# MCU_adacus_sch.net
KiCad netlist of a schematic drawn in Altium Designer
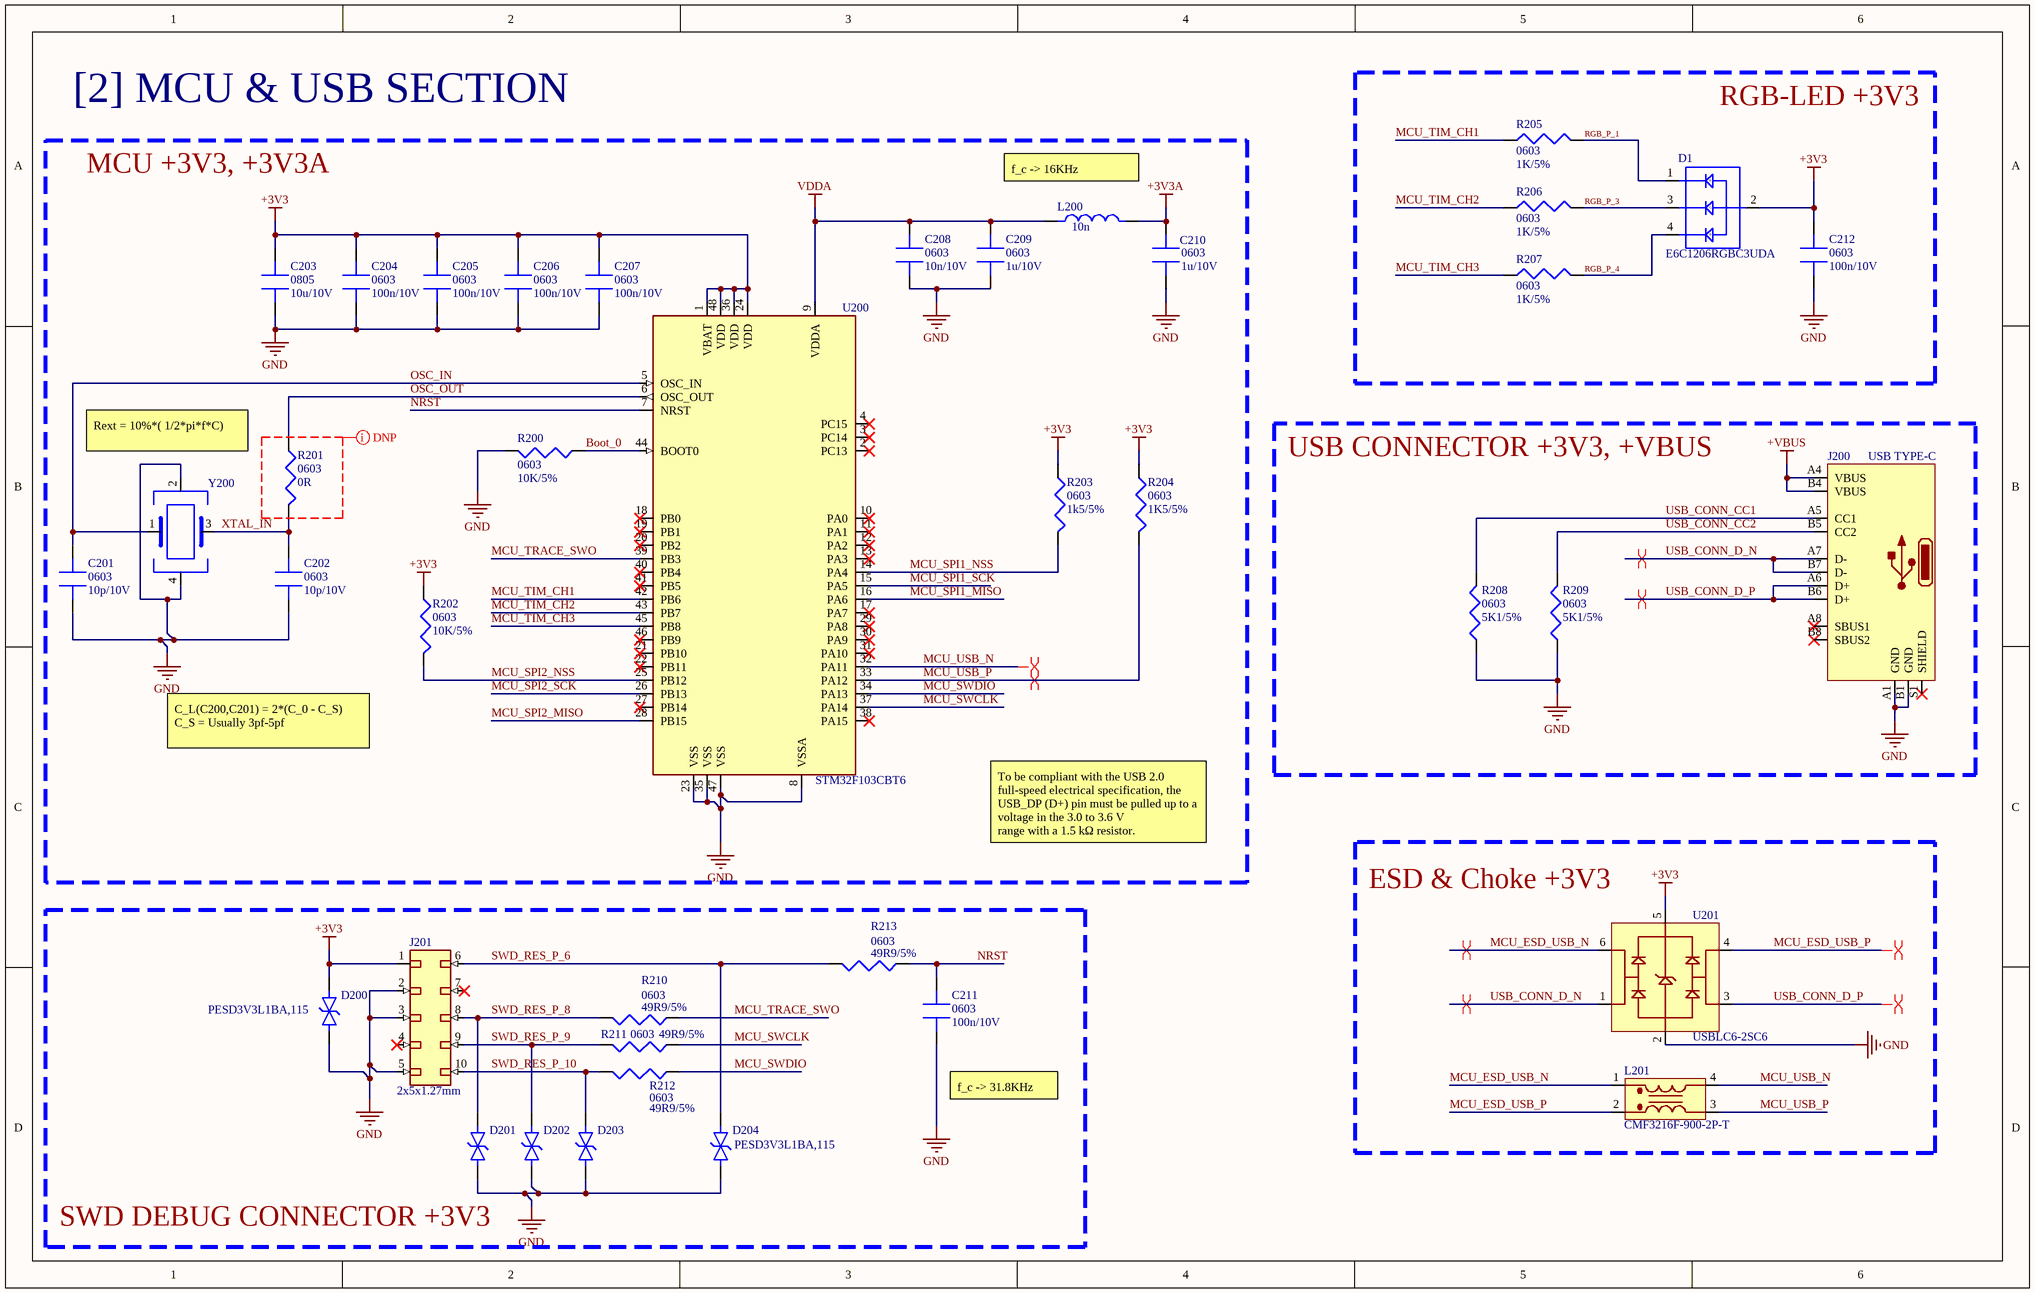
[diagram p0: MCU_adacus_sch.SchDoc]

(export (version "E")
  (design (tool "Eeschema 10.0.6"))
  (components
    (comp (ref "C201")
      (value "10p/10V")
      (footprint "[0603] CAPC1608X10M [A-LD]")
      (description "Standard Capacitor")
      (fields (field (name "PACKAGE") "0603") (field (name "Comment") "Capacitor"))
      (libsource (lib "adacus_schlib") (part "Capacitor"))
    )
    (comp (ref "C202")
      (value "10p/10V")
      (footprint "[0603] CAPC1608X10M [A-LD]")
      (description "Standard Capacitor")
      (fields (field (name "PACKAGE") "0603") (field (name "Comment") "Capacitor"))
      (libsource (lib "adacus_schlib") (part "Capacitor"))
    )
    (comp (ref "C203")
      (value "10u/10V")
      (footprint "[0805] CAPC2012X09M [A - LD]")
      (description "Standard Capacitor")
      (fields (field (name "PACKAGE") "0805") (field (name "Comment") "Capacitor"))
      (libsource (lib "adacus_schlib") (part "Capacitor"))
    )
    (comp (ref "C204")
      (value "100n/10V")
      (footprint "[0603] CAPC1608X10M [A-LD]")
      (description "Standard Capacitor")
      (fields (field (name "PACKAGE") "0603") (field (name "Comment") "Capacitor"))
      (libsource (lib "adacus_schlib") (part "Capacitor"))
    )
    (comp (ref "C205")
      (value "100n/10V")
      (footprint "[0603] CAPC1608X10M [A-LD]")
      (description "Standard Capacitor")
      (fields (field (name "PACKAGE") "0603") (field (name "Comment") "Capacitor"))
      (libsource (lib "adacus_schlib") (part "Capacitor"))
    )
    (comp (ref "C206")
      (value "100n/10V")
      (footprint "[0603] CAPC1608X10M [A-LD]")
      (description "Standard Capacitor")
      (fields (field (name "PACKAGE") "0603") (field (name "Comment") "Capacitor"))
      (libsource (lib "adacus_schlib") (part "Capacitor"))
    )
    (comp (ref "C207")
      (value "100n/10V")
      (footprint "[0603] CAPC1608X10M [A-LD]")
      (description "Standard Capacitor")
      (fields (field (name "PACKAGE") "0603") (field (name "Comment") "Capacitor"))
      (libsource (lib "adacus_schlib") (part "Capacitor"))
    )
    (comp (ref "C208")
      (value "10n/10V")
      (footprint "[0603] CAPC1608X10M [A-LD]")
      (description "Standard Capacitor")
      (fields (field (name "PACKAGE") "0603") (field (name "Comment") "Capacitor"))
      (libsource (lib "adacus_schlib") (part "Capacitor"))
    )
    (comp (ref "C209")
      (value "1u/10V")
      (footprint "[0603] CAPC1608X10M [A-LD]")
      (description "Standard Capacitor")
      (fields (field (name "PACKAGE") "0603") (field (name "Comment") "Capacitor"))
      (libsource (lib "adacus_schlib") (part "Capacitor"))
    )
    (comp (ref "C210")
      (value "1u/10V")
      (footprint "[0603] CAPC1608X10M [A-LD]")
      (description "Standard Capacitor")
      (fields (field (name "PACKAGE") "0603") (field (name "Comment") "Capacitor"))
      (libsource (lib "adacus_schlib") (part "Capacitor"))
    )
    (comp (ref "C211")
      (value "100n/10V")
      (footprint "[0603] CAPC1608X10M [A-LD]")
      (description "Standard Capacitor")
      (fields (field (name "PACKAGE") "0603") (field (name "Comment") "Capacitor"))
      (libsource (lib "adacus_schlib") (part "Capacitor"))
    )
    (comp (ref "C212")
      (value "100n/10V")
      (footprint "[0603] CAPC1608X10M [A-LD]")
      (description "Standard Capacitor")
      (fields (field (name "PACKAGE") "0603") (field (name "Comment") "Capacitor"))
      (libsource (lib "adacus_schlib") (part "Capacitor"))
    )
    (comp (ref "D1")
      (value "E6C1206RGBC3UDA")
      (footprint "E6C1206RGBC3UDA")
      (description "RGB 1206 Light Emitting Diodes (LED) ROHS")
      (libsource (lib "adacus_schlib") (part "LED_RGB"))
    )
    (comp (ref "D200")
      (value "PESD3V3L1BA,115")
      (footprint "SODFL250X110-2M")
      (description "ESD Suppressors / TVS Diodes PESD3V3L1BA/SOD323/SOD2")
      (libsource (lib "adacus_schlib") (part "PESD3V3L1BA,115"))
    )
    (comp (ref "D201")
      (value "PESD3V3L1BA,115")
      (footprint "SODFL250X110-2M")
      (description "ESD Suppressors / TVS Diodes PESD3V3L1BA/SOD323/SOD2")
      (libsource (lib "adacus_schlib") (part "PESD3V3L1BA,115"))
    )
    (comp (ref "D202")
      (value "PESD3V3L1BA,115")
      (footprint "SODFL250X110-2M")
      (description "ESD Suppressors / TVS Diodes PESD3V3L1BA/SOD323/SOD2")
      (libsource (lib "adacus_schlib") (part "PESD3V3L1BA,115"))
    )
    (comp (ref "D203")
      (value "PESD3V3L1BA,115")
      (footprint "SODFL250X110-2M")
      (description "ESD Suppressors / TVS Diodes PESD3V3L1BA/SOD323/SOD2")
      (libsource (lib "adacus_schlib") (part "PESD3V3L1BA,115"))
    )
    (comp (ref "D204")
      (value "PESD3V3L1BA,115")
      (footprint "SODFL250X110-2M")
      (description "ESD Suppressors / TVS Diodes PESD3V3L1BA/SOD323/SOD2")
      (libsource (lib "adacus_schlib") (part "PESD3V3L1BA,115"))
    )
    (comp (ref "J200")
      (value "USB TYPE-C")
      (footprint "HRO_TYPE-C-31-M-12")
      (libsource (lib "adacus_schlib") (part "USB TYPE-C"))
    )
    (comp (ref "J201")
      (value "2x5x1.27mm")
      (footprint "2X10_BOXHEADER")
      (description "SWD Connector 2x5x1.27mm pin count")
      (libsource (lib "adacus_schlib") (part "SWD Connector"))
    )
    (comp (ref "L200")
      (value "10n")
      (footprint "PM0603-10NJ")
      (description "Standard Inductor")
      (fields (field (name "Comment") "Inductor"))
      (libsource (lib "adacus_schlib") (part "Inductor"))
    )
    (comp (ref "L201")
      (value "CMF3216F-900-2P-T")
      (footprint "CMF3216F-900-2P-T")
      (description "90Ω@100MHz 0.3Ω 2 1206 Common Mode Filters ROHS")
      (libsource (lib "adacus_schlib") (part "CMF3216F-900-2P-T"))
    )
    (comp (ref "R200")
      (value "10K/5%")
      (footprint "[0603] RESC1608X06M [A-LD]")
      (description "Standard Resistor")
      (fields (field (name "PACKAGE") "0603") (field (name "Comment") "Resistor"))
      (libsource (lib "adacus_schlib") (part "Resistor"))
    )
    (comp (ref "R201")
      (value "0R")
      (footprint "[0603] RESC1608X06M [A-LD]")
      (description "Standard Resistor")
      (fields (field (name "PACKAGE") "0603") (field (name "Comment") "Resistor"))
      (libsource (lib "adacus_schlib") (part "Resistor"))
    )
    (comp (ref "R202")
      (value "10K/5%")
      (footprint "[0603] RESC1608X06M [A-LD]")
      (description "Standard Resistor")
      (fields (field (name "PACKAGE") "0603") (field (name "Comment") "Resistor"))
      (libsource (lib "adacus_schlib") (part "Resistor"))
    )
    (comp (ref "R203")
      (value "1k5/5%")
      (footprint "[0603] RESC1608X06M [A-LD]")
      (description "Standard Resistor")
      (fields (field (name "PACKAGE") "0603") (field (name "Comment") "Resistor"))
      (libsource (lib "adacus_schlib") (part "Resistor"))
    )
    (comp (ref "R204")
      (value "1K5/5%")
      (footprint "[0603] RESC1608X06M [A-LD]")
      (description "Standard Resistor")
      (fields (field (name "PACKAGE") "0603") (field (name "Comment") "Resistor"))
      (libsource (lib "adacus_schlib") (part "Resistor"))
    )
    (comp (ref "R205")
      (value "1K/5%")
      (footprint "[0603] RESC1608X06M [A-LD]")
      (description "Standard Resistor")
      (fields (field (name "PACKAGE") "0603") (field (name "Comment") "Resistor"))
      (libsource (lib "adacus_schlib") (part "Resistor"))
    )
    (comp (ref "R206")
      (value "1K/5%")
      (footprint "[0603] RESC1608X06M [A-LD]")
      (description "Standard Resistor")
      (fields (field (name "PACKAGE") "0603") (field (name "Comment") "Resistor"))
      (libsource (lib "adacus_schlib") (part "Resistor"))
    )
    (comp (ref "R207")
      (value "1K/5%")
      (footprint "[0603] RESC1608X06M [A-LD]")
      (description "Standard Resistor")
      (fields (field (name "PACKAGE") "0603") (field (name "Comment") "Resistor"))
      (libsource (lib "adacus_schlib") (part "Resistor"))
    )
    (comp (ref "R208")
      (value "5K1/5%")
      (footprint "[0603] RESC1608X06M [A-LD]")
      (description "Standard Resistor")
      (fields (field (name "PACKAGE") "0603") (field (name "Comment") "Resistor"))
      (libsource (lib "adacus_schlib") (part "Resistor"))
    )
    (comp (ref "R209")
      (value "5K1/5%")
      (footprint "[0603] RESC1608X06M [A-LD]")
      (description "Standard Resistor")
      (fields (field (name "PACKAGE") "0603") (field (name "Comment") "Resistor"))
      (libsource (lib "adacus_schlib") (part "Resistor"))
    )
    (comp (ref "R210")
      (value "49R9/5%")
      (footprint "[0603] RESC1608X06M [A-LD]")
      (description "Standard Resistor")
      (fields (field (name "PACKAGE") "0603") (field (name "Comment") "Resistor"))
      (libsource (lib "adacus_schlib") (part "Resistor"))
    )
    (comp (ref "R211")
      (value "49R9/5%")
      (footprint "[0603] RESC1608X06M [A-LD]")
      (description "Standard Resistor")
      (fields (field (name "PACKAGE") "0603") (field (name "Comment") "Resistor"))
      (libsource (lib "adacus_schlib") (part "Resistor"))
    )
    (comp (ref "R212")
      (value "49R9/5%")
      (footprint "[0603] RESC1608X06M [A-LD]")
      (description "Standard Resistor")
      (fields (field (name "PACKAGE") "0603") (field (name "Comment") "Resistor"))
      (libsource (lib "adacus_schlib") (part "Resistor"))
    )
    (comp (ref "R213")
      (value "49R9/5%")
      (footprint "[0603] RESC1608X06M [A-LD]")
      (description "Standard Resistor")
      (fields (field (name "PACKAGE") "0603") (field (name "Comment") "Resistor"))
      (libsource (lib "adacus_schlib") (part "Resistor"))
    )
    (comp (ref "U200")
      (value "STM32F103CBT6")
      (footprint "TSQFP50P900X900X160-48M")
      (description "ARM Microcontrollers - MCU 32BIT Cortex M3 128K MED Performance LN")
      (libsource (lib "adacus_schlib") (part "STM32F103CBT6"))
    )
    (comp (ref "U201")
      (value "USBLC6-2SC6")
      (footprint "SOT95P280X145-6M")
      (description "Very low capacitance ESD protection")
      (libsource (lib "adacus_schlib") (part "USBLC6-2"))
    )
    (comp (ref "Y200")
      (value "ECS-2016MV-160-DN")
      (footprint "ECS-2016MV-160-DN")
      (libsource (lib "adacus_schlib") (part "ECS-2016MV-160-DN"))
    )
  )
  (nets
    (net (code "1") (name "+3V3") (class "Default")
      (node (ref "C203") (pin "2") (pinfunction "2_2") (pintype "passive"))
      (node (ref "C204") (pin "2") (pinfunction "2_2") (pintype "passive"))
      (node (ref "C205") (pin "2") (pinfunction "2_2") (pintype "passive"))
      (node (ref "C206") (pin "2") (pinfunction "2_2") (pintype "passive"))
      (node (ref "C207") (pin "2") (pinfunction "2_2") (pintype "passive"))
      (node (ref "C212") (pin "2") (pinfunction "2_2") (pintype "passive"))
      (node (ref "D1") (pin "2") (pinfunction "2_2") (pintype "passive"))
      (node (ref "D200") (pin "2") (pinfunction "2_2") (pintype "passive"))
      (node (ref "J201") (pin "1") (pinfunction "VCC_1") (pintype "power_in"))
      (node (ref "R202") (pin "2") (pinfunction "2_2") (pintype "passive"))
      (node (ref "R203") (pin "2") (pinfunction "2_2") (pintype "passive"))
      (node (ref "R204") (pin "2") (pinfunction "2_2") (pintype "passive"))
      (node (ref "U200") (pin "1") (pinfunction "VBAT_1") (pintype "power_in"))
      (node (ref "U200") (pin "24") (pinfunction "VDD_24") (pintype "power_in"))
      (node (ref "U200") (pin "36") (pinfunction "VDD_36") (pintype "power_in"))
      (node (ref "U200") (pin "48") (pinfunction "VDD_48") (pintype "power_in"))
      (node (ref "U201") (pin "5") (pinfunction "5_5") (pintype "passive"))
    )
    (net (code "2") (name "+3V3A") (class "Default")
      (node (ref "C210") (pin "2") (pinfunction "2_2") (pintype "passive"))
      (node (ref "L200") (pin "1") (pinfunction "1_1") (pintype "passive"))
    )
    (net (code "3") (name "+VBUS") (class "Default")
      (node (ref "J200") (pin "A4") (pinfunction "VBUS_A4") (pintype "passive"))
      (node (ref "J200") (pin "B4") (pinfunction "VBUS_B4") (pintype "passive"))
    )
    (net (code "4") (name "/Boot_0") (class "Default")
      (node (ref "R200") (pin "2") (pinfunction "2_2") (pintype "passive"))
      (node (ref "U200") (pin "44") (pinfunction "BOOT0_44") (pintype "input"))
    )
    (net (code "5") (name "/MCU_ESD_USB_N") (class "Default")
      (node (ref "L201") (pin "1") (pinfunction "1_1") (pintype "passive"))
      (node (ref "U201") (pin "6") (pinfunction "6_6") (pintype "passive"))
    )
    (net (code "6") (name "/MCU_ESD_USB_P") (class "Default")
      (node (ref "L201") (pin "2") (pinfunction "2_2") (pintype "passive"))
      (node (ref "U201") (pin "4") (pinfunction "4_4") (pintype "passive"))
    )
    (net (code "7") (name "/MCU_SPI1_MISO") (class "Default")
      (node (ref "U200") (pin "16") (pinfunction "PA6_16") (pintype "bidirectional"))
    )
    (net (code "8") (name "/MCU_SPI1_NSS") (class "Default")
      (node (ref "R203") (pin "1") (pinfunction "1_1") (pintype "passive"))
      (node (ref "U200") (pin "14") (pinfunction "PA4_14") (pintype "bidirectional"))
    )
    (net (code "9") (name "/MCU_SPI1_SCK") (class "Default")
      (node (ref "U200") (pin "15") (pinfunction "PA5_15") (pintype "bidirectional"))
    )
    (net (code "10") (name "/MCU_SPI2_MISO") (class "Default")
      (node (ref "U200") (pin "28") (pinfunction "PB15_28") (pintype "bidirectional"))
    )
    (net (code "11") (name "/MCU_SPI2_NSS") (class "Default")
      (node (ref "R202") (pin "1") (pinfunction "1_1") (pintype "passive"))
      (node (ref "U200") (pin "25") (pinfunction "PB12_25") (pintype "bidirectional"))
    )
    (net (code "12") (name "/MCU_SPI2_SCK") (class "Default")
      (node (ref "U200") (pin "26") (pinfunction "PB13_26") (pintype "bidirectional"))
    )
    (net (code "13") (name "/MCU_SWCLK") (class "Default")
      (node (ref "R211") (pin "2") (pinfunction "2_2") (pintype "passive"))
      (node (ref "U200") (pin "37") (pinfunction "PA14_37") (pintype "bidirectional"))
    )
    (net (code "14") (name "/MCU_SWDIO") (class "Default")
      (node (ref "R212") (pin "2") (pinfunction "2_2") (pintype "passive"))
      (node (ref "U200") (pin "34") (pinfunction "PA13_34") (pintype "bidirectional"))
    )
    (net (code "15") (name "/MCU_TIM_CH1") (class "Default")
      (node (ref "R205") (pin "2") (pinfunction "2_2") (pintype "passive"))
      (node (ref "U200") (pin "42") (pinfunction "PB6_42") (pintype "bidirectional"))
    )
    (net (code "16") (name "/MCU_TIM_CH2") (class "Default")
      (node (ref "R206") (pin "2") (pinfunction "2_2") (pintype "passive"))
      (node (ref "U200") (pin "43") (pinfunction "PB7_43") (pintype "bidirectional"))
    )
    (net (code "17") (name "/MCU_TIM_CH3") (class "Default")
      (node (ref "R207") (pin "2") (pinfunction "2_2") (pintype "passive"))
      (node (ref "U200") (pin "45") (pinfunction "PB8_45") (pintype "bidirectional"))
    )
    (net (code "18") (name "/MCU_TRACE_SWO") (class "Default")
      (node (ref "R210") (pin "2") (pinfunction "2_2") (pintype "passive"))
      (node (ref "U200") (pin "39") (pinfunction "PB3_39") (pintype "bidirectional"))
    )
    (net (code "19") (name "/MCU_USB_N") (class "Default")
      (node (ref "L201") (pin "4") (pinfunction "4_4") (pintype "passive"))
      (node (ref "U200") (pin "32") (pinfunction "PA11_32") (pintype "bidirectional"))
    )
    (net (code "20") (name "/MCU_USB_P") (class "Default")
      (node (ref "L201") (pin "3") (pinfunction "3_3") (pintype "passive"))
      (node (ref "R204") (pin "1") (pinfunction "1_1") (pintype "passive"))
      (node (ref "U200") (pin "33") (pinfunction "PA12_33") (pintype "bidirectional"))
    )
    (net (code "21") (name "/NRST") (class "Default")
      (node (ref "C211") (pin "2") (pinfunction "2_2") (pintype "passive"))
      (node (ref "R213") (pin "2") (pinfunction "2_2") (pintype "passive"))
      (node (ref "U200") (pin "7") (pinfunction "NRST_7") (pintype "bidirectional"))
    )
    (net (code "22") (name "/OSC_IN") (class "Default")
      (node (ref "C201") (pin "2") (pinfunction "2_2") (pintype "passive"))
      (node (ref "U200") (pin "5") (pinfunction "OSC_IN_5") (pintype "input"))
      (node (ref "Y200") (pin "1") (pinfunction "1_1") (pintype "passive"))
    )
    (net (code "23") (name "/OSC_OUT") (class "Default")
      (node (ref "R201") (pin "2") (pinfunction "2_2") (pintype "passive"))
      (node (ref "U200") (pin "6") (pinfunction "OSC_OUT_6") (pintype "output"))
    )
    (net (code "24") (name "/RGB_P_1") (class "Default")
      (node (ref "D1") (pin "1") (pinfunction "1_1") (pintype "passive"))
      (node (ref "R205") (pin "1") (pinfunction "1_1") (pintype "passive"))
    )
    (net (code "25") (name "/RGB_P_3") (class "Default")
      (node (ref "D1") (pin "3") (pinfunction "3_3") (pintype "passive"))
      (node (ref "R206") (pin "1") (pinfunction "1_1") (pintype "passive"))
    )
    (net (code "26") (name "/RGB_P_4") (class "Default")
      (node (ref "D1") (pin "4") (pinfunction "4_4") (pintype "passive"))
      (node (ref "R207") (pin "1") (pinfunction "1_1") (pintype "passive"))
    )
    (net (code "27") (name "/SWD_RES_P_6") (class "Default")
      (node (ref "D204") (pin "2") (pinfunction "2_2") (pintype "passive"))
      (node (ref "J201") (pin "6") (pinfunction "TDO_6") (pintype "input"))
      (node (ref "R213") (pin "1") (pinfunction "1_1") (pintype "passive"))
    )
    (net (code "28") (name "/SWD_RES_P_8") (class "Default")
      (node (ref "D201") (pin "2") (pinfunction "2_2") (pintype "passive"))
      (node (ref "J201") (pin "8") (pinfunction "TDI_8") (pintype "input"))
      (node (ref "R210") (pin "1") (pinfunction "1_1") (pintype "passive"))
    )
    (net (code "29") (name "/SWD_RES_P_9") (class "Default")
      (node (ref "D202") (pin "2") (pinfunction "2_2") (pintype "passive"))
      (node (ref "J201") (pin "9") (pinfunction "GND_9") (pintype "input"))
      (node (ref "R211") (pin "1") (pinfunction "1_1") (pintype "passive"))
    )
    (net (code "30") (name "/SWD_RES_P_10") (class "Default")
      (node (ref "D203") (pin "2") (pinfunction "2_2") (pintype "passive"))
      (node (ref "J201") (pin "10") (pinfunction "nRESET_10") (pintype "input"))
      (node (ref "R212") (pin "1") (pinfunction "1_1") (pintype "passive"))
    )
    (net (code "31") (name "/USB_CONN_CC1") (class "Default")
      (node (ref "J200") (pin "A5") (pinfunction "CC1_A5") (pintype "passive"))
      (node (ref "R208") (pin "1") (pinfunction "1_1") (pintype "passive"))
    )
    (net (code "32") (name "/USB_CONN_CC2") (class "Default")
      (node (ref "J200") (pin "B5") (pinfunction "CC2_B5") (pintype "passive"))
      (node (ref "R209") (pin "1") (pinfunction "1_1") (pintype "passive"))
    )
    (net (code "33") (name "/USB_CONN_D_N") (class "Default")
      (node (ref "J200") (pin "A7") (pinfunction "D-_A7") (pintype "passive"))
      (node (ref "J200") (pin "B7") (pinfunction "D-_B7") (pintype "passive"))
      (node (ref "U201") (pin "1") (pinfunction "1_1") (pintype "passive"))
    )
    (net (code "34") (name "/USB_CONN_D_P") (class "Default")
      (node (ref "J200") (pin "A6") (pinfunction "D+_A6") (pintype "passive"))
      (node (ref "J200") (pin "B6") (pinfunction "D+_B6") (pintype "passive"))
      (node (ref "U201") (pin "3") (pinfunction "3_3") (pintype "passive"))
    )
    (net (code "35") (name "/XTAL_IN") (class "Default")
      (node (ref "C202") (pin "2") (pinfunction "2_2") (pintype "passive"))
      (node (ref "R201") (pin "1") (pinfunction "1_1") (pintype "passive"))
      (node (ref "Y200") (pin "3") (pinfunction "3_3") (pintype "passive"))
    )
    (net (code "36") (name "GND") (class "Default")
      (node (ref "C201") (pin "1") (pinfunction "1_1") (pintype "passive"))
      (node (ref "C202") (pin "1") (pinfunction "1_1") (pintype "passive"))
      (node (ref "C203") (pin "1") (pinfunction "1_1") (pintype "passive"))
      (node (ref "C204") (pin "1") (pinfunction "1_1") (pintype "passive"))
      (node (ref "C205") (pin "1") (pinfunction "1_1") (pintype "passive"))
      (node (ref "C206") (pin "1") (pinfunction "1_1") (pintype "passive"))
      (node (ref "C207") (pin "1") (pinfunction "1_1") (pintype "passive"))
      (node (ref "C208") (pin "1") (pinfunction "1_1") (pintype "passive"))
      (node (ref "C209") (pin "1") (pinfunction "1_1") (pintype "passive"))
      (node (ref "C210") (pin "1") (pinfunction "1_1") (pintype "passive"))
      (node (ref "C211") (pin "1") (pinfunction "1_1") (pintype "passive"))
      (node (ref "C212") (pin "1") (pinfunction "1_1") (pintype "passive"))
      (node (ref "D200") (pin "1") (pinfunction "1_1") (pintype "passive"))
      (node (ref "D201") (pin "1") (pinfunction "1_1") (pintype "passive"))
      (node (ref "D202") (pin "1") (pinfunction "1_1") (pintype "passive"))
      (node (ref "D203") (pin "1") (pinfunction "1_1") (pintype "passive"))
      (node (ref "D204") (pin "1") (pinfunction "1_1") (pintype "passive"))
      (node (ref "J200") (pin "A1") (pinfunction "GND_A1") (pintype "passive"))
      (node (ref "J200") (pin "B1") (pinfunction "GND_B1") (pintype "passive"))
      (node (ref "J201") (pin "2") (pinfunction "TMS_2") (pintype "input"))
      (node (ref "J201") (pin "3") (pinfunction "GND_3") (pintype "input"))
      (node (ref "J201") (pin "5") (pinfunction "GND_5") (pintype "input"))
      (node (ref "R200") (pin "1") (pinfunction "1_1") (pintype "passive"))
      (node (ref "R208") (pin "2") (pinfunction "2_2") (pintype "passive"))
      (node (ref "R209") (pin "2") (pinfunction "2_2") (pintype "passive"))
      (node (ref "U200") (pin "23") (pinfunction "VSS_23") (pintype "power_in"))
      (node (ref "U200") (pin "35") (pinfunction "VSS_35") (pintype "power_in"))
      (node (ref "U200") (pin "47") (pinfunction "VSS_47") (pintype "power_in"))
      (node (ref "U200") (pin "8") (pinfunction "VSSA_8") (pintype "power_in"))
      (node (ref "U201") (pin "2") (pinfunction "2_2") (pintype "passive"))
      (node (ref "Y200") (pin "2") (pinfunction "3_2") (pintype "passive"))
      (node (ref "Y200") (pin "4") (pinfunction "4_4") (pintype "passive"))
    )
    (net (code "37") (name "VDDA") (class "Default")
      (node (ref "C208") (pin "2") (pinfunction "2_2") (pintype "passive"))
      (node (ref "C209") (pin "2") (pinfunction "2_2") (pintype "passive"))
      (node (ref "L200") (pin "2") (pinfunction "2_2") (pintype "passive"))
      (node (ref "U200") (pin "9") (pinfunction "VDDA_9") (pintype "power_in"))
    )
    (net (code "38") (name "unconnected-(J200-SBUS1-PadA8)") (class "Default")
      (node (ref "J200") (pin "A8") (pinfunction "SBUS1_A8") (pintype "passive+no_connect"))
    )
    (net (code "39") (name "unconnected-(J200-SBUS2-PadB8)") (class "Default")
      (node (ref "J200") (pin "B8") (pinfunction "SBUS2_B8") (pintype "passive+no_connect"))
    )
    (net (code "40") (name "unconnected-(J200-SHIELD-PadS1)") (class "Default")
      (node (ref "J200") (pin "S1") (pinfunction "SHIELD_S1") (pintype "passive+no_connect"))
    )
    (net (code "41") (name "unconnected-(J201-KEY-Pad7)") (class "Default")
      (node (ref "J201") (pin "7") (pinfunction "KEY_7") (pintype "input+no_connect"))
    )
    (net (code "42") (name "unconnected-(J201-TCK-Pad4)") (class "Default")
      (node (ref "J201") (pin "4") (pinfunction "TCK_4") (pintype "input+no_connect"))
    )
    (net (code "43") (name "unconnected-(U200-PA0-Pad10)") (class "Default")
      (node (ref "U200") (pin "10") (pinfunction "PA0_10") (pintype "bidirectional+no_connect"))
    )
    (net (code "44") (name "unconnected-(U200-PA1-Pad11)") (class "Default")
      (node (ref "U200") (pin "11") (pinfunction "PA1_11") (pintype "bidirectional+no_connect"))
    )
    (net (code "45") (name "unconnected-(U200-PA2-Pad12)") (class "Default")
      (node (ref "U200") (pin "12") (pinfunction "PA2_12") (pintype "bidirectional+no_connect"))
    )
    (net (code "46") (name "unconnected-(U200-PA3-Pad13)") (class "Default")
      (node (ref "U200") (pin "13") (pinfunction "PA3_13") (pintype "bidirectional+no_connect"))
    )
    (net (code "47") (name "unconnected-(U200-PA7-Pad17)") (class "Default")
      (node (ref "U200") (pin "17") (pinfunction "PA7_17") (pintype "bidirectional+no_connect"))
    )
    (net (code "48") (name "unconnected-(U200-PA8-Pad29)") (class "Default")
      (node (ref "U200") (pin "29") (pinfunction "PA8_29") (pintype "bidirectional+no_connect"))
    )
    (net (code "49") (name "unconnected-(U200-PA9-Pad30)") (class "Default")
      (node (ref "U200") (pin "30") (pinfunction "PA9_30") (pintype "bidirectional+no_connect"))
    )
    (net (code "50") (name "unconnected-(U200-PA10-Pad31)") (class "Default")
      (node (ref "U200") (pin "31") (pinfunction "PA10_31") (pintype "bidirectional+no_connect"))
    )
    (net (code "51") (name "unconnected-(U200-PA15-Pad38)") (class "Default")
      (node (ref "U200") (pin "38") (pinfunction "PA15_38") (pintype "bidirectional+no_connect"))
    )
    (net (code "52") (name "unconnected-(U200-PB0-Pad18)") (class "Default")
      (node (ref "U200") (pin "18") (pinfunction "PB0_18") (pintype "bidirectional+no_connect"))
    )
    (net (code "53") (name "unconnected-(U200-PB1-Pad19)") (class "Default")
      (node (ref "U200") (pin "19") (pinfunction "PB1_19") (pintype "bidirectional+no_connect"))
    )
    (net (code "54") (name "unconnected-(U200-PB2-Pad20)") (class "Default")
      (node (ref "U200") (pin "20") (pinfunction "PB2_20") (pintype "bidirectional+no_connect"))
    )
    (net (code "55") (name "unconnected-(U200-PB4-Pad40)") (class "Default")
      (node (ref "U200") (pin "40") (pinfunction "PB4_40") (pintype "bidirectional+no_connect"))
    )
    (net (code "56") (name "unconnected-(U200-PB5-Pad41)") (class "Default")
      (node (ref "U200") (pin "41") (pinfunction "PB5_41") (pintype "bidirectional+no_connect"))
    )
    (net (code "57") (name "unconnected-(U200-PB9-Pad46)") (class "Default")
      (node (ref "U200") (pin "46") (pinfunction "PB9_46") (pintype "bidirectional+no_connect"))
    )
    (net (code "58") (name "unconnected-(U200-PB10-Pad21)") (class "Default")
      (node (ref "U200") (pin "21") (pinfunction "PB10_21") (pintype "bidirectional+no_connect"))
    )
    (net (code "59") (name "unconnected-(U200-PB11-Pad22)") (class "Default")
      (node (ref "U200") (pin "22") (pinfunction "PB11_22") (pintype "bidirectional+no_connect"))
    )
    (net (code "60") (name "unconnected-(U200-PB14-Pad27)") (class "Default")
      (node (ref "U200") (pin "27") (pinfunction "PB14_27") (pintype "bidirectional+no_connect"))
    )
    (net (code "61") (name "unconnected-(U200-PC13-Pad2)") (class "Default")
      (node (ref "U200") (pin "2") (pinfunction "PC13_2") (pintype "bidirectional+no_connect"))
    )
    (net (code "62") (name "unconnected-(U200-PC14-Pad3)") (class "Default")
      (node (ref "U200") (pin "3") (pinfunction "PC14_3") (pintype "bidirectional+no_connect"))
    )
    (net (code "63") (name "unconnected-(U200-PC15-Pad4)") (class "Default")
      (node (ref "U200") (pin "4") (pinfunction "PC15_4") (pintype "bidirectional+no_connect"))
    )
  )
)
